# Weather_Station.net
KiCad netlist of a schematic drawn in EAGLE
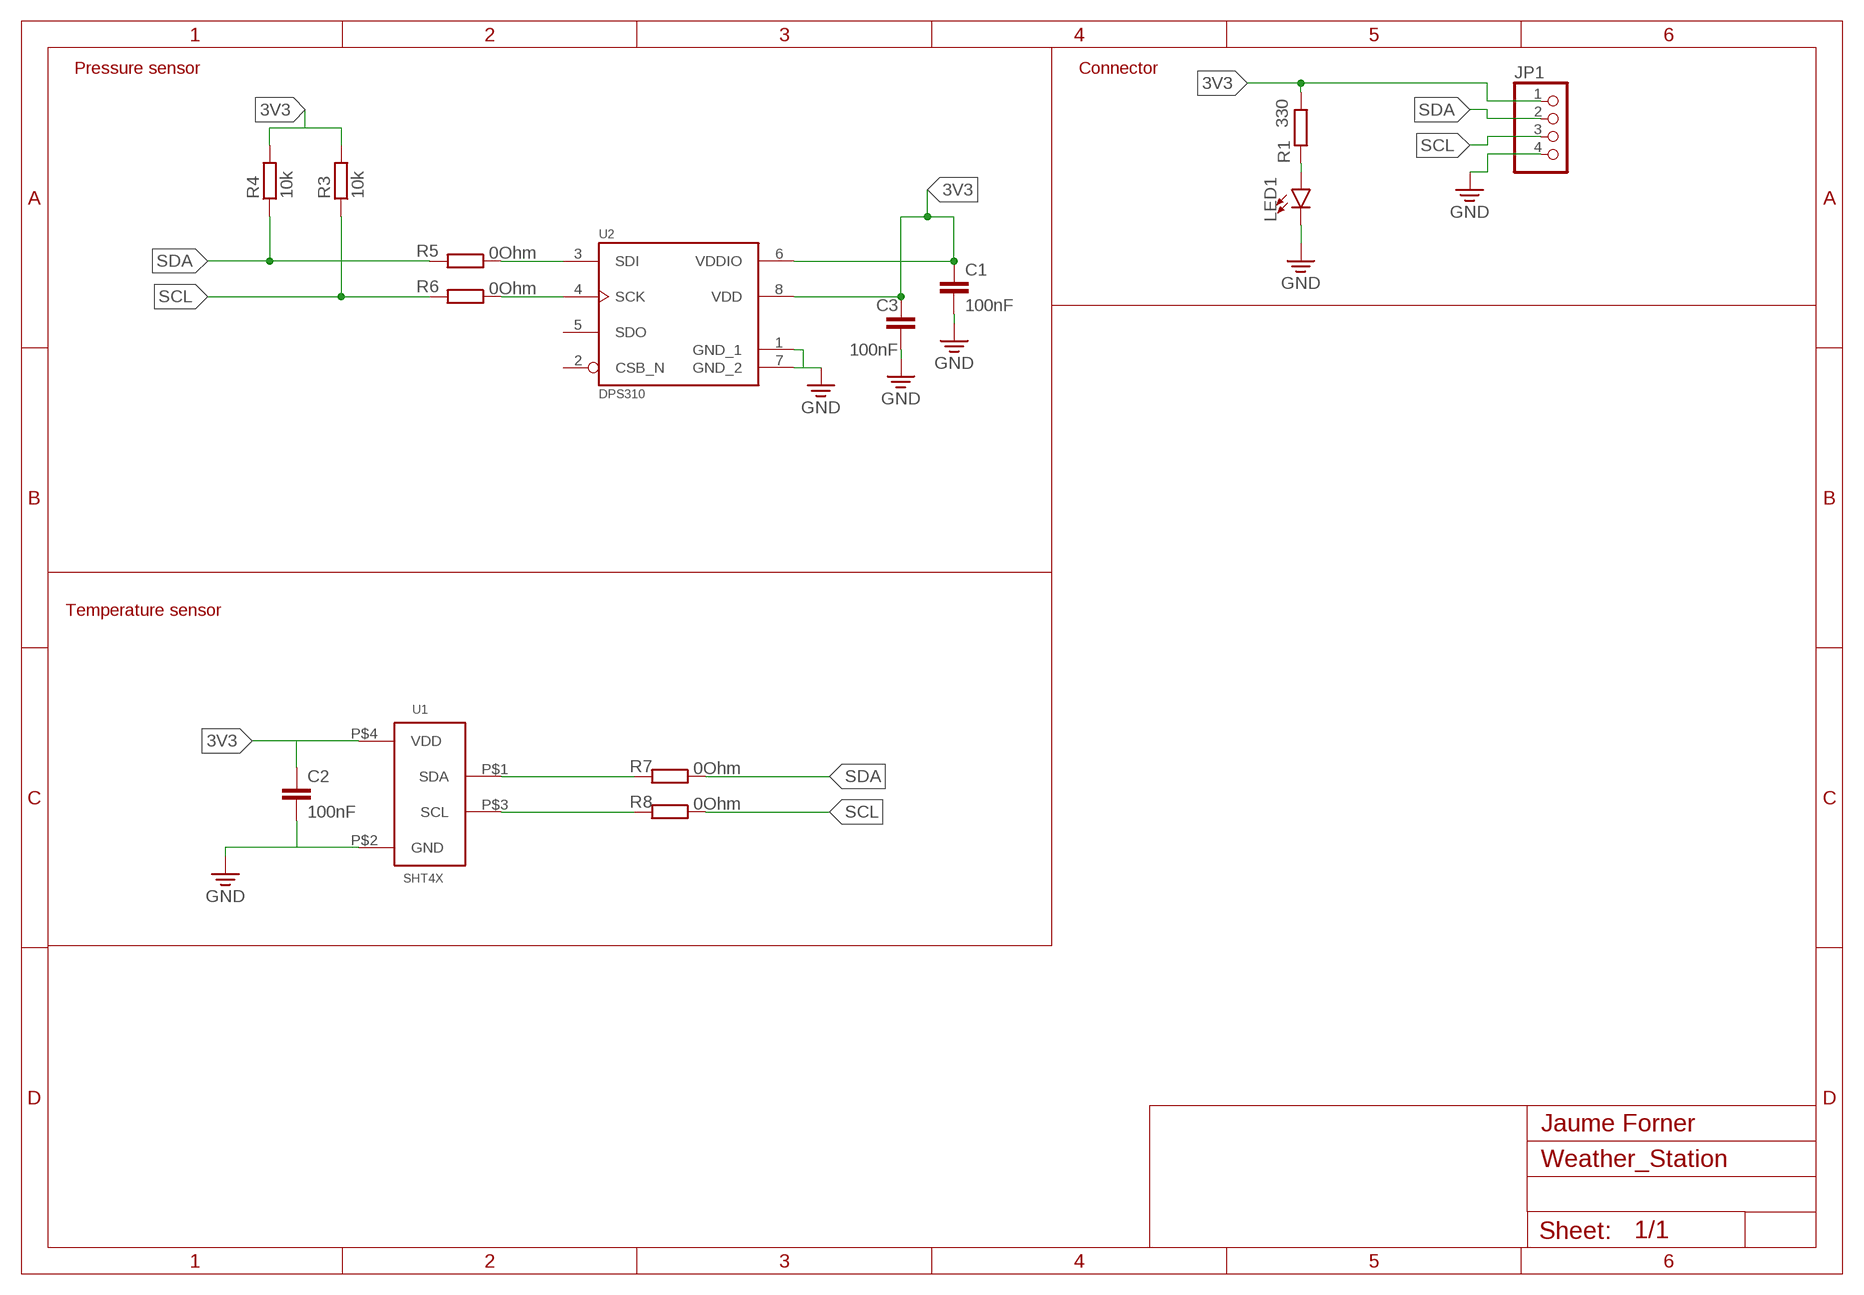
[diagram p0: schematic, sheet 1]

(export (version "E")
  (design (tool "Eeschema 10.0.6"))
  (components
    (comp (ref "C1")
      (value "100nF")
      (footprint "eagle-import:C0603K")
      (libsource (lib "eagle-import") (part "C-EUC0603K"))
    )
    (comp (ref "C2")
      (value "100nF")
      (footprint "eagle-import:C0603K")
      (libsource (lib "eagle-import") (part "C-EUC0603K"))
    )
    (comp (ref "C3")
      (value "100nF")
      (footprint "eagle-import:C0603K")
      (libsource (lib "eagle-import") (part "C-EUC0603K"))
    )
    (comp (ref "JP1")
      (value "PINHD-1X4")
      (footprint "eagle-import:1X04")
      (libsource (lib "eagle-import") (part "PINHD-1X4"))
    )
    (comp (ref "LED1")
      (value "LED0603")
      (footprint "eagle-import:LED-0603")
      (libsource (lib "eagle-import") (part "LED0603"))
    )
    (comp (ref "R1")
      (value "330")
      (footprint "eagle-import:R0603")
      (libsource (lib "eagle-import") (part "R-EU_R0603"))
    )
    (comp (ref "R3")
      (value "10k")
      (footprint "eagle-import:R0603")
      (libsource (lib "eagle-import") (part "R-EU_R0603"))
    )
    (comp (ref "R4")
      (value "10k")
      (footprint "eagle-import:R0603")
      (libsource (lib "eagle-import") (part "R-EU_R0603"))
    )
    (comp (ref "R5")
      (value "0Ohm")
      (footprint "eagle-import:R0603")
      (libsource (lib "eagle-import") (part "R-EU_R0603"))
    )
    (comp (ref "R6")
      (value "0Ohm")
      (footprint "eagle-import:R0603")
      (libsource (lib "eagle-import") (part "R-EU_R0603"))
    )
    (comp (ref "R7")
      (value "0Ohm")
      (footprint "eagle-import:R0603")
      (libsource (lib "eagle-import") (part "R-EU_R0603"))
    )
    (comp (ref "R8")
      (value "0Ohm")
      (footprint "eagle-import:R0603")
      (libsource (lib "eagle-import") (part "R-EU_R0603"))
    )
    (comp (ref "U1")
      (value "SHT4X")
      (footprint "eagle-import:SHT40-SHT41")
      (libsource (lib "eagle-import") (part "SHT4X"))
    )
    (comp (ref "U2")
      (value "DPS310")
      (footprint "eagle-import:LGA8S145X65P2X4_200X250X110-V")
      (libsource (lib "eagle-import") (part "DPS310"))
    )
  )
  (nets
    (net (code "1") (name "3V3") (class "Default")
      (node (ref "C1") (pin "1") (pinfunction "1_1") (pintype "passive"))
      (node (ref "C2") (pin "1") (pinfunction "1_1") (pintype "passive"))
      (node (ref "C3") (pin "1") (pinfunction "1_1") (pintype "passive"))
      (node (ref "JP1") (pin "1") (pinfunction "1_1") (pintype "passive"))
      (node (ref "R1") (pin "1") (pinfunction "1_1") (pintype "passive"))
      (node (ref "R3") (pin "2") (pinfunction "2_2") (pintype "passive"))
      (node (ref "R4") (pin "2") (pinfunction "2_2") (pintype "passive"))
      (node (ref "U1") (pin "P$4") (pinfunction "VDD_P$4") (pintype "bidirectional"))
      (node (ref "U2") (pin "6") (pinfunction "VDDIO_6") (pintype "power_in"))
      (node (ref "U2") (pin "8") (pinfunction "VDD_8") (pintype "power_in"))
    )
    (net (code "2") (name "GND") (class "Default")
      (node (ref "C1") (pin "2") (pinfunction "2_2") (pintype "passive"))
      (node (ref "C2") (pin "2") (pinfunction "2_2") (pintype "passive"))
      (node (ref "C3") (pin "2") (pinfunction "2_2") (pintype "passive"))
      (node (ref "JP1") (pin "4") (pinfunction "4_4") (pintype "passive"))
      (node (ref "LED1") (pin "C") (pinfunction "C_C") (pintype "passive"))
      (node (ref "U1") (pin "P$2") (pinfunction "GND_P$2") (pintype "bidirectional"))
      (node (ref "U2") (pin "1") (pinfunction "GND_1_1") (pintype "power_in"))
      (node (ref "U2") (pin "7") (pinfunction "GND_2_7") (pintype "power_in"))
    )
    (net (code "3") (name "Net-(LED1-PadA)") (class "Default")
      (node (ref "LED1") (pin "A") (pinfunction "A_A") (pintype "passive"))
      (node (ref "R1") (pin "2") (pinfunction "2_2") (pintype "passive"))
    )
    (net (code "4") (name "Net-(U1-SCL)") (class "Default")
      (node (ref "R8") (pin "2") (pinfunction "2_2") (pintype "passive"))
      (node (ref "U1") (pin "P$3") (pinfunction "SCL_P$3") (pintype "bidirectional"))
    )
    (net (code "5") (name "Net-(U1-SDA)") (class "Default")
      (node (ref "R7") (pin "2") (pinfunction "2_2") (pintype "passive"))
      (node (ref "U1") (pin "P$1") (pinfunction "SDA_P$1") (pintype "bidirectional"))
    )
    (net (code "6") (name "Net-(U2-SCK)") (class "Default")
      (node (ref "R6") (pin "1") (pinfunction "1_1") (pintype "passive"))
      (node (ref "U2") (pin "4") (pinfunction "SCK_4") (pintype "input"))
    )
    (net (code "7") (name "Net-(U2-SDI)") (class "Default")
      (node (ref "R5") (pin "1") (pinfunction "1_1") (pintype "passive"))
      (node (ref "U2") (pin "3") (pinfunction "SDI_3") (pintype "bidirectional"))
    )
    (net (code "8") (name "SCL") (class "Default")
      (node (ref "JP1") (pin "3") (pinfunction "3_3") (pintype "passive"))
      (node (ref "R3") (pin "1") (pinfunction "1_1") (pintype "passive"))
      (node (ref "R6") (pin "2") (pinfunction "2_2") (pintype "passive"))
      (node (ref "R8") (pin "1") (pinfunction "1_1") (pintype "passive"))
    )
    (net (code "9") (name "SDA") (class "Default")
      (node (ref "JP1") (pin "2") (pinfunction "2_2") (pintype "passive"))
      (node (ref "R4") (pin "1") (pinfunction "1_1") (pintype "passive"))
      (node (ref "R5") (pin "2") (pinfunction "2_2") (pintype "passive"))
      (node (ref "R7") (pin "1") (pinfunction "1_1") (pintype "passive"))
    )
    (net (code "10") (name "unconnected-(U2-CSB_N-Pad2)") (class "Default")
      (node (ref "U2") (pin "2") (pinfunction "CSB_N_2") (pintype "input"))
    )
    (net (code "11") (name "unconnected-(U2-SDO-Pad5)") (class "Default")
      (node (ref "U2") (pin "5") (pinfunction "SDO_5") (pintype "output"))
    )
  )
)
